# DIP20-2-2_54.net
KiCad netlist of a schematic drawn in EAGLE
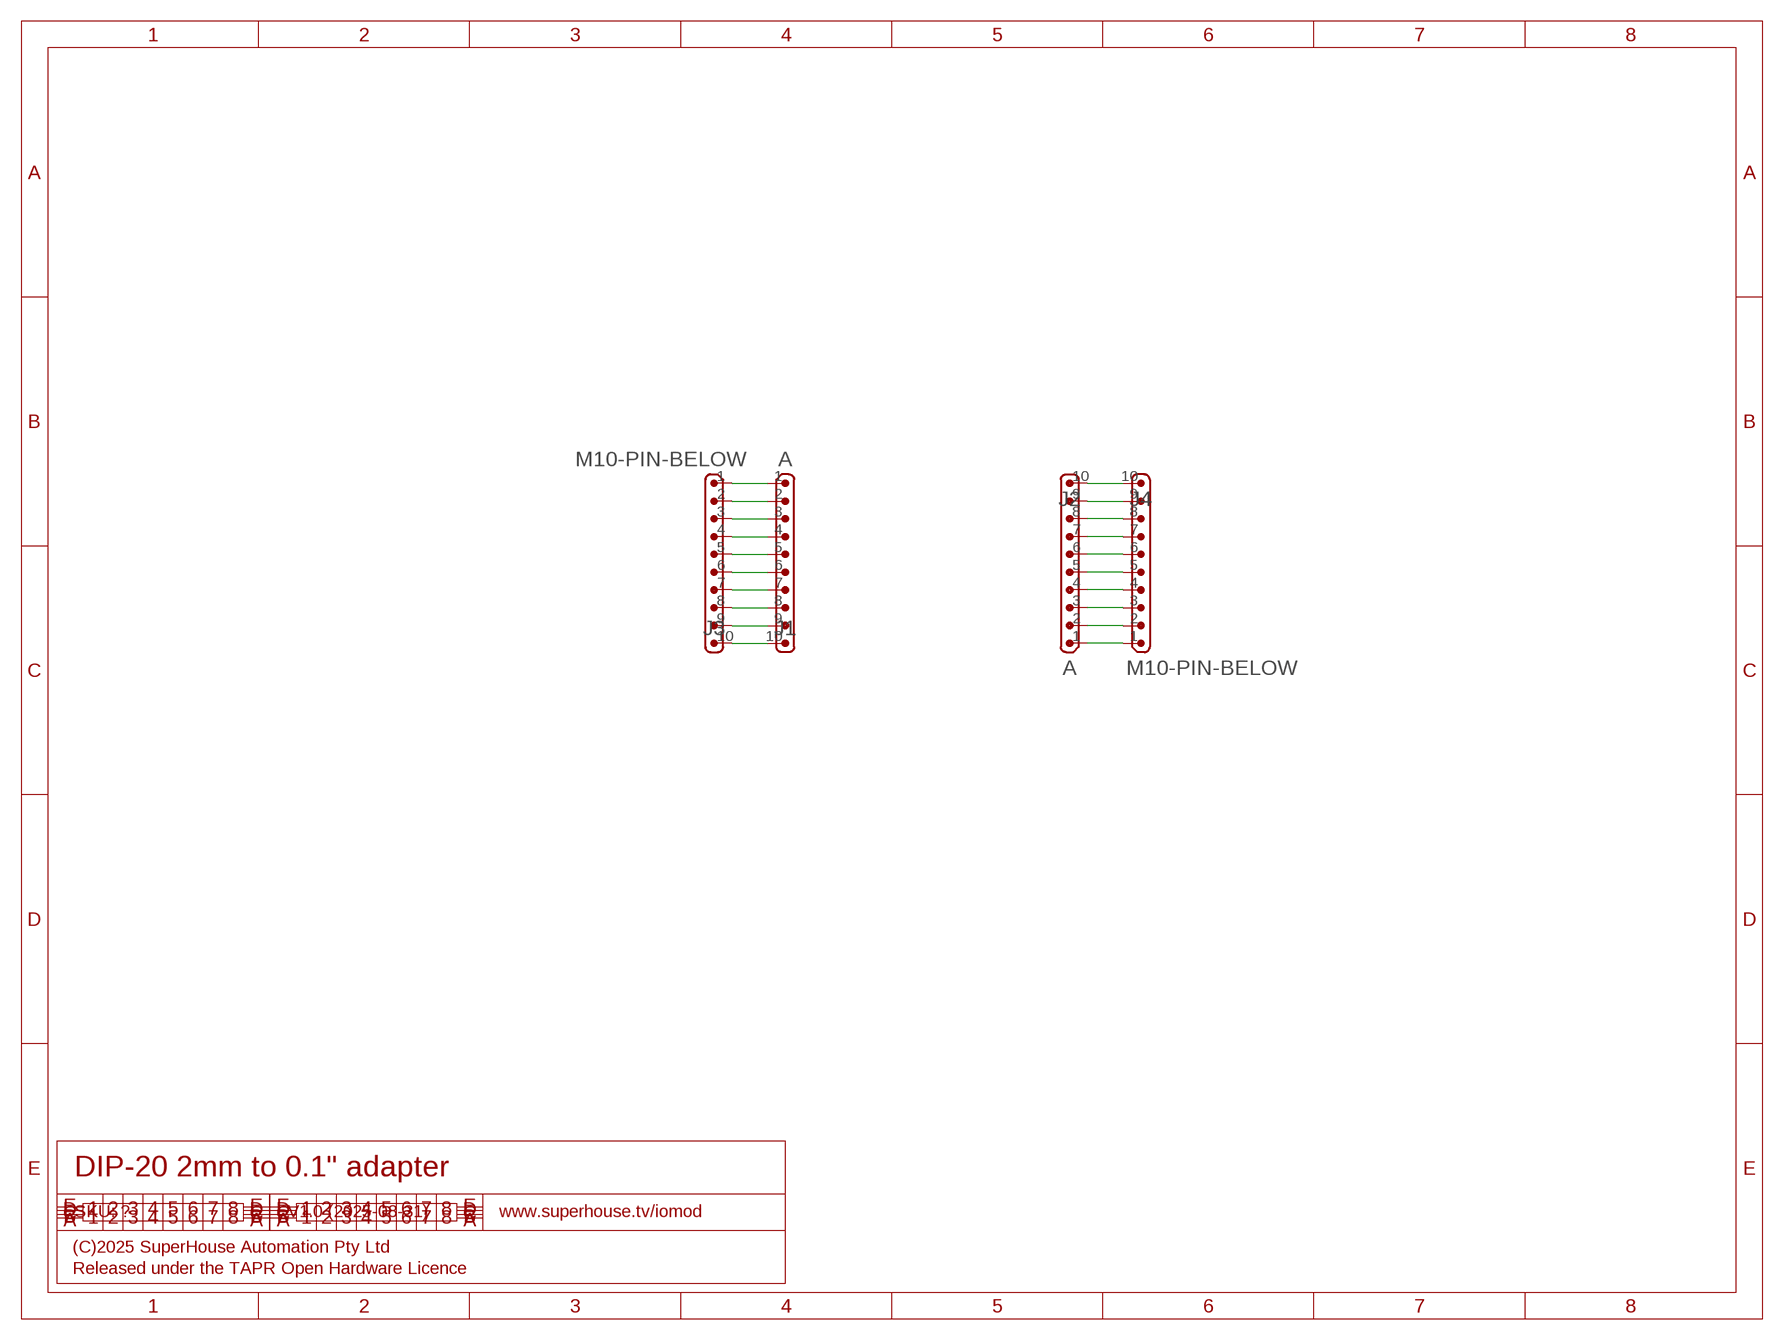
[diagram p0: schematic, sheet 1]

(export (version "E")
  (design (tool "Eeschema 10.0.6"))
  (components
    (comp (ref "J1")
      (value "A")
      (footprint "eagle-import:1X10-2.00-S")
      (libsource (lib "eagle-import") (part "M10-2.00-S"))
    )
    (comp (ref "J2")
      (value "A")
      (footprint "eagle-import:1X10-2.00-S")
      (libsource (lib "eagle-import") (part "M10-2.00-S"))
    )
    (comp (ref "J3")
      (value "M10-PIN-BELOW")
      (footprint "eagle-import:1X10-P-BELOW")
      (libsource (lib "eagle-import") (part "M10-PIN-BELOW"))
    )
    (comp (ref "J4")
      (value "M10-PIN-BELOW")
      (footprint "eagle-import:1X10-P-BELOW")
      (libsource (lib "eagle-import") (part "M10-PIN-BELOW"))
    )
  )
  (nets
    (net (code "1") (name "Net-(J1-Pad1)") (class "Default")
      (node (ref "J1") (pin "1") (pinfunction "1_1") (pintype "passive"))
      (node (ref "J3") (pin "1") (pinfunction "1_1") (pintype "passive"))
    )
    (net (code "2") (name "Net-(J1-Pad2)") (class "Default")
      (node (ref "J1") (pin "2") (pinfunction "2_2") (pintype "passive"))
      (node (ref "J3") (pin "2") (pinfunction "2_2") (pintype "passive"))
    )
    (net (code "3") (name "Net-(J1-Pad3)") (class "Default")
      (node (ref "J1") (pin "3") (pinfunction "3_3") (pintype "passive"))
      (node (ref "J3") (pin "3") (pinfunction "3_3") (pintype "passive"))
    )
    (net (code "4") (name "Net-(J1-Pad4)") (class "Default")
      (node (ref "J1") (pin "4") (pinfunction "4_4") (pintype "passive"))
      (node (ref "J3") (pin "4") (pinfunction "4_4") (pintype "passive"))
    )
    (net (code "5") (name "Net-(J1-Pad5)") (class "Default")
      (node (ref "J1") (pin "5") (pinfunction "5_5") (pintype "passive"))
      (node (ref "J3") (pin "5") (pinfunction "5_5") (pintype "passive"))
    )
    (net (code "6") (name "Net-(J1-Pad6)") (class "Default")
      (node (ref "J1") (pin "6") (pinfunction "6_6") (pintype "passive"))
      (node (ref "J3") (pin "6") (pinfunction "6_6") (pintype "passive"))
    )
    (net (code "7") (name "Net-(J1-Pad7)") (class "Default")
      (node (ref "J1") (pin "7") (pinfunction "7_7") (pintype "passive"))
      (node (ref "J3") (pin "7") (pinfunction "7_7") (pintype "passive"))
    )
    (net (code "8") (name "Net-(J1-Pad8)") (class "Default")
      (node (ref "J1") (pin "8") (pinfunction "8_8") (pintype "passive"))
      (node (ref "J3") (pin "8") (pinfunction "8_8") (pintype "passive"))
    )
    (net (code "9") (name "Net-(J1-Pad9)") (class "Default")
      (node (ref "J1") (pin "9") (pinfunction "9_9") (pintype "passive"))
      (node (ref "J3") (pin "9") (pinfunction "9_9") (pintype "passive"))
    )
    (net (code "10") (name "Net-(J1-Pad10)") (class "Default")
      (node (ref "J1") (pin "10") (pinfunction "10_10") (pintype "passive"))
      (node (ref "J3") (pin "10") (pinfunction "10_10") (pintype "passive"))
    )
    (net (code "11") (name "Net-(J2-Pad1)") (class "Default")
      (node (ref "J2") (pin "1") (pinfunction "1_1") (pintype "passive"))
      (node (ref "J4") (pin "1") (pinfunction "1_1") (pintype "passive"))
    )
    (net (code "12") (name "Net-(J2-Pad2)") (class "Default")
      (node (ref "J2") (pin "2") (pinfunction "2_2") (pintype "passive"))
      (node (ref "J4") (pin "2") (pinfunction "2_2") (pintype "passive"))
    )
    (net (code "13") (name "Net-(J2-Pad3)") (class "Default")
      (node (ref "J2") (pin "3") (pinfunction "3_3") (pintype "passive"))
      (node (ref "J4") (pin "3") (pinfunction "3_3") (pintype "passive"))
    )
    (net (code "14") (name "Net-(J2-Pad4)") (class "Default")
      (node (ref "J2") (pin "4") (pinfunction "4_4") (pintype "passive"))
      (node (ref "J4") (pin "4") (pinfunction "4_4") (pintype "passive"))
    )
    (net (code "15") (name "Net-(J2-Pad5)") (class "Default")
      (node (ref "J2") (pin "5") (pinfunction "5_5") (pintype "passive"))
      (node (ref "J4") (pin "5") (pinfunction "5_5") (pintype "passive"))
    )
    (net (code "16") (name "Net-(J2-Pad6)") (class "Default")
      (node (ref "J2") (pin "6") (pinfunction "6_6") (pintype "passive"))
      (node (ref "J4") (pin "6") (pinfunction "6_6") (pintype "passive"))
    )
    (net (code "17") (name "Net-(J2-Pad7)") (class "Default")
      (node (ref "J2") (pin "7") (pinfunction "7_7") (pintype "passive"))
      (node (ref "J4") (pin "7") (pinfunction "7_7") (pintype "passive"))
    )
    (net (code "18") (name "Net-(J2-Pad8)") (class "Default")
      (node (ref "J2") (pin "8") (pinfunction "8_8") (pintype "passive"))
      (node (ref "J4") (pin "8") (pinfunction "8_8") (pintype "passive"))
    )
    (net (code "19") (name "Net-(J2-Pad9)") (class "Default")
      (node (ref "J2") (pin "9") (pinfunction "9_9") (pintype "passive"))
      (node (ref "J4") (pin "9") (pinfunction "9_9") (pintype "passive"))
    )
    (net (code "20") (name "Net-(J2-Pad10)") (class "Default")
      (node (ref "J2") (pin "10") (pinfunction "10_10") (pintype "passive"))
      (node (ref "J4") (pin "10") (pinfunction "10_10") (pintype "passive"))
    )
  )
)
